# IO_PWR_FMU_REV_2A.net
KiCad netlist of a schematic drawn in Altium Designer
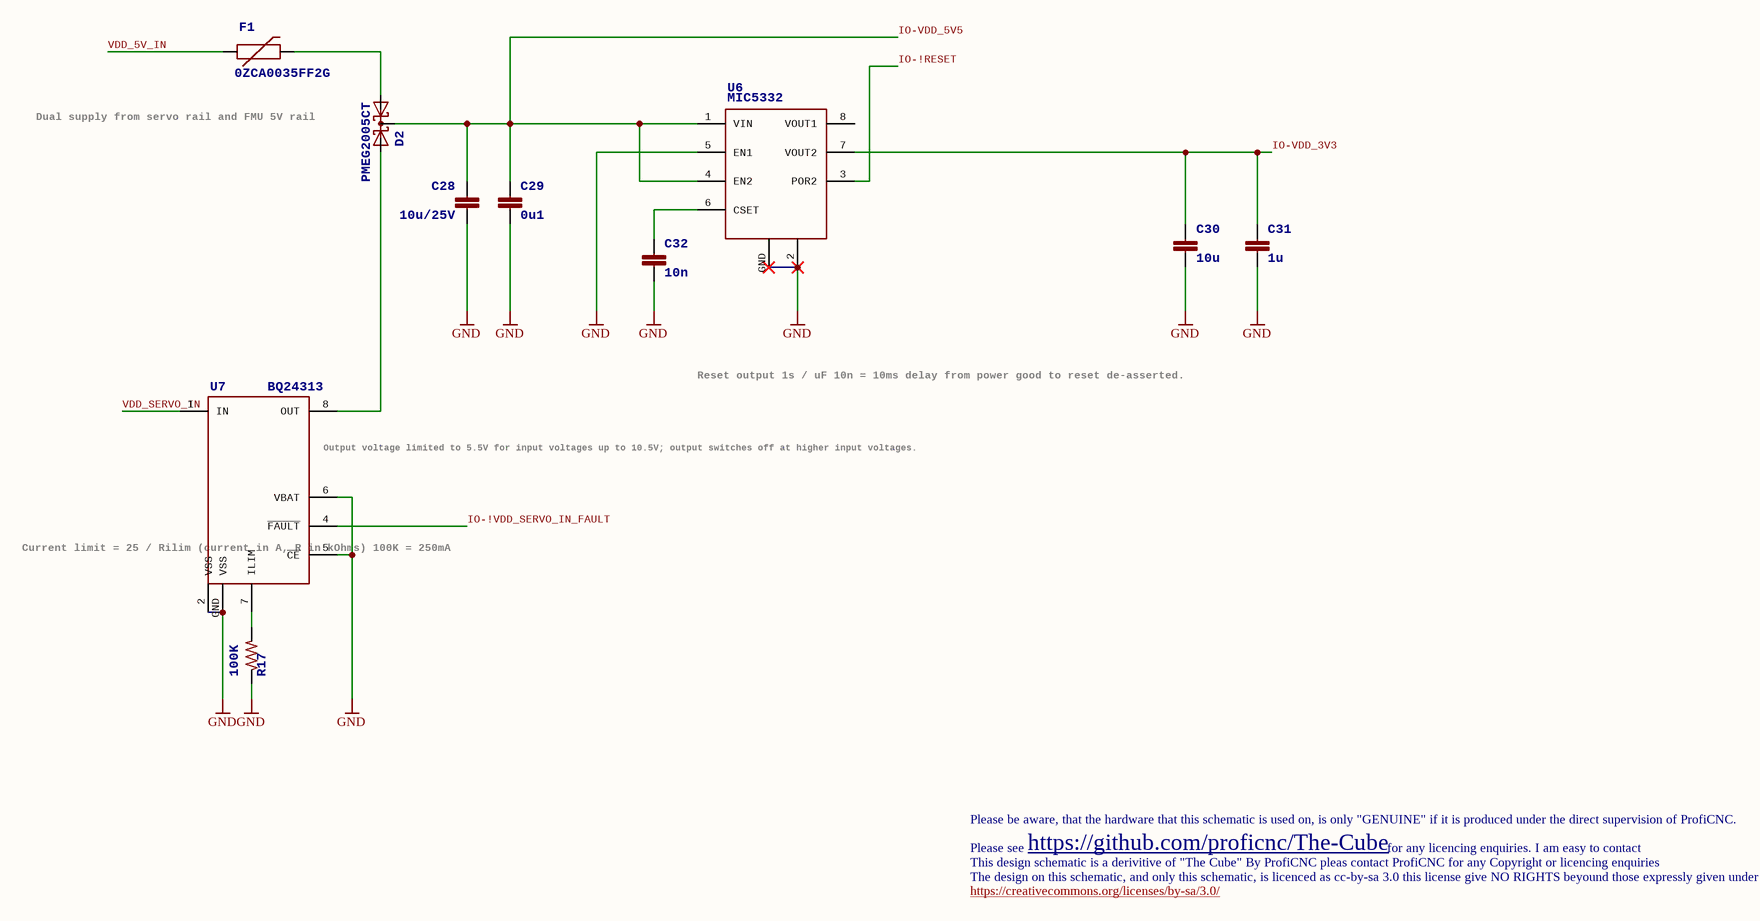
[diagram p0: IO_PWR_FMU_REV_2A.SchDoc]

(export (version "E")
  (design (tool "Eeschema 10.0.6"))
  (components
    (comp (ref "C28")
      (value "10u/25V")
      (footprint "0805-CAP")
      (description "CAP CER 10UF 25V 10% X5R 0805")
      (libsource (lib "pixhawk2") (part "CAP0805"))
    )
    (comp (ref "C29")
      (value "0u1")
      (footprint "0402-CAP")
      (description "CAP CER 0.1UF 16V Y5V 0402")
      (libsource (lib "pixhawk2") (part "CAP0402"))
    )
    (comp (ref "C30")
      (value "10u")
      (footprint "0603-CAP")
      (description "CAP CER 10UF 10V 10% X5R 0603")
      (libsource (lib "pixhawk2") (part "CAP0603"))
    )
    (comp (ref "C31")
      (value "1u")
      (footprint "0603-CAP")
      (description "CAP CER 1UF 16V Y5V 0603")
      (libsource (lib "pixhawk2") (part "CAP0603"))
    )
    (comp (ref "C32")
      (value "10n")
      (footprint "0402-CAP")
      (description "CAP CER 10000PF 16V 10% X7R 0402")
      (libsource (lib "pixhawk2") (part "CAP0402"))
    )
    (comp (ref "D2")
      (value "PMEG2005CT")
      (footprint "SOT23-3")
      (description "DIODE SCHOTTKY 20V 500MA TO236AB")
      (libsource (lib "pixhawk2") (part "PMEG2005CT"))
    )
    (comp (ref "F1")
      (value "0ZCA0035FF2G")
      (footprint "PTC-1206")
      (description "PTC RESTTBLE 0.35A 16V CHIP 1206")
      (libsource (lib "pixhawk2") (part "PTCSMD"))
    )
    (comp (ref "Logo1")
      (value "ProfiCNC_LOGO")
      (footprint "ProfiCNC_medium")
      (libsource (lib "ProfiCNC") (part "ProfiCNC_LOGO"))
    )
    (comp (ref "R17")
      (value "100K")
      (footprint "0402-RES")
      (description "RES 100K OHM 1/16W 1% 0402 SMD")
      (libsource (lib "pixhawk2") (part "RESISTOR0402-RES"))
    )
    (comp (ref "U6")
      (value "MIC5332")
      (footprint "MLF-8-EPAD")
      (description "IC REG LDO 3.3V 0.3A 8TMLF")
      (libsource (lib "pixhawk2") (part "MIC5332"))
    )
    (comp (ref "U7")
      (value "BQ24313")
      (footprint "QFN8-DSG")
      (description "IC LI+ CHARGER FRONT END 8-SON")
      (libsource (lib "pixhawk2") (part "BQ24313"))
    )
  )
  (nets
    (net (code "1") (name "/IO-!RESET") (class "Default")
      (node (ref "U6") (pin "3") (pinfunction "POR2_3") (pintype "passive"))
    )
    (net (code "2") (name "/IO-!VDD_SERVO_IN_FAULT") (class "Default")
      (node (ref "U7") (pin "4") (pinfunction "~{FAULT}_4") (pintype "passive"))
    )
    (net (code "3") (name "/IO-VDD_3V3") (class "Default")
      (node (ref "C30") (pin "P$1") (pinfunction "1_P$1") (pintype "passive"))
      (node (ref "C31") (pin "P$1") (pinfunction "1_P$1") (pintype "passive"))
      (node (ref "U6") (pin "7") (pinfunction "VOUT2_7") (pintype "passive"))
    )
    (net (code "4") (name "/IO-VDD_5V5") (class "Default")
      (node (ref "C28") (pin "P$1") (pinfunction "1_P$1") (pintype "passive"))
      (node (ref "C29") (pin "P$1") (pinfunction "1_P$1") (pintype "passive"))
      (node (ref "D2") (pin "3") (pinfunction "CC_3") (pintype "passive"))
      (node (ref "U6") (pin "1") (pinfunction "VIN_1") (pintype "passive"))
      (node (ref "U6") (pin "4") (pinfunction "EN2_4") (pintype "passive"))
    )
    (net (code "5") (name "/VDD_5V_IN") (class "Default")
      (node (ref "F1") (pin "1") (pinfunction "1_1") (pintype "passive"))
    )
    (net (code "6") (name "/VDD_SERVO_IN") (class "Default")
      (node (ref "U7") (pin "1") (pinfunction "IN_1") (pintype "passive"))
    )
    (net (code "7") (name "GND") (class "Default")
      (node (ref "C28") (pin "P$2") (pinfunction "2_P$2") (pintype "passive"))
      (node (ref "C29") (pin "P$2") (pinfunction "2_P$2") (pintype "passive"))
      (node (ref "C30") (pin "P$2") (pinfunction "2_P$2") (pintype "passive"))
      (node (ref "C31") (pin "P$2") (pinfunction "2_P$2") (pintype "passive"))
      (node (ref "C32") (pin "P$2") (pinfunction "2_P$2") (pintype "passive"))
      (node (ref "R17") (pin "P$1") (pinfunction "1_P$1") (pintype "passive"))
      (node (ref "U6") (pin "2") (pinfunction "GND_2") (pintype "power_in"))
      (node (ref "U6") (pin "5") (pinfunction "EN1_5") (pintype "passive"))
      (node (ref "U6") (pin "GND") (pinfunction "GND_GND") (pintype "power_in"))
      (node (ref "U7") (pin "2") (pinfunction "VSS_2") (pintype "passive"))
      (node (ref "U7") (pin "5") (pinfunction "~{CE}_5") (pintype "passive"))
      (node (ref "U7") (pin "6") (pinfunction "VBAT_6") (pintype "passive"))
      (node (ref "U7") (pin "GND") (pinfunction "VSS_GND") (pintype "passive"))
    )
    (net (code "8") (name "Net-(C32-1)") (class "Default")
      (node (ref "C32") (pin "P$1") (pinfunction "1_P$1") (pintype "passive"))
      (node (ref "U6") (pin "6") (pinfunction "CSET_6") (pintype "passive"))
    )
    (net (code "9") (name "Net-(D2-A1)") (class "Default")
      (node (ref "D2") (pin "1") (pinfunction "A1_1") (pintype "passive"))
      (node (ref "F1") (pin "2") (pinfunction "2_2") (pintype "passive"))
    )
    (net (code "10") (name "Net-(D2-A2)") (class "Default")
      (node (ref "D2") (pin "2") (pinfunction "A2_2") (pintype "passive"))
      (node (ref "U7") (pin "8") (pinfunction "OUT_8") (pintype "passive"))
    )
    (net (code "11") (name "Net-(R17-2)") (class "Default")
      (node (ref "R17") (pin "P$2") (pinfunction "2_P$2") (pintype "passive"))
      (node (ref "U7") (pin "7") (pinfunction "ILIM_7") (pintype "passive"))
    )
    (net (code "12") (name "unconnected-(U6-VOUT1-Pad8)") (class "Default")
      (node (ref "U6") (pin "8") (pinfunction "VOUT1_8") (pintype "passive"))
    )
  )
)
